# TIDA-01576_ADS8686S_AFE_Pg6-Current_Meas.net
KiCad netlist of a schematic drawn in Altium Designer
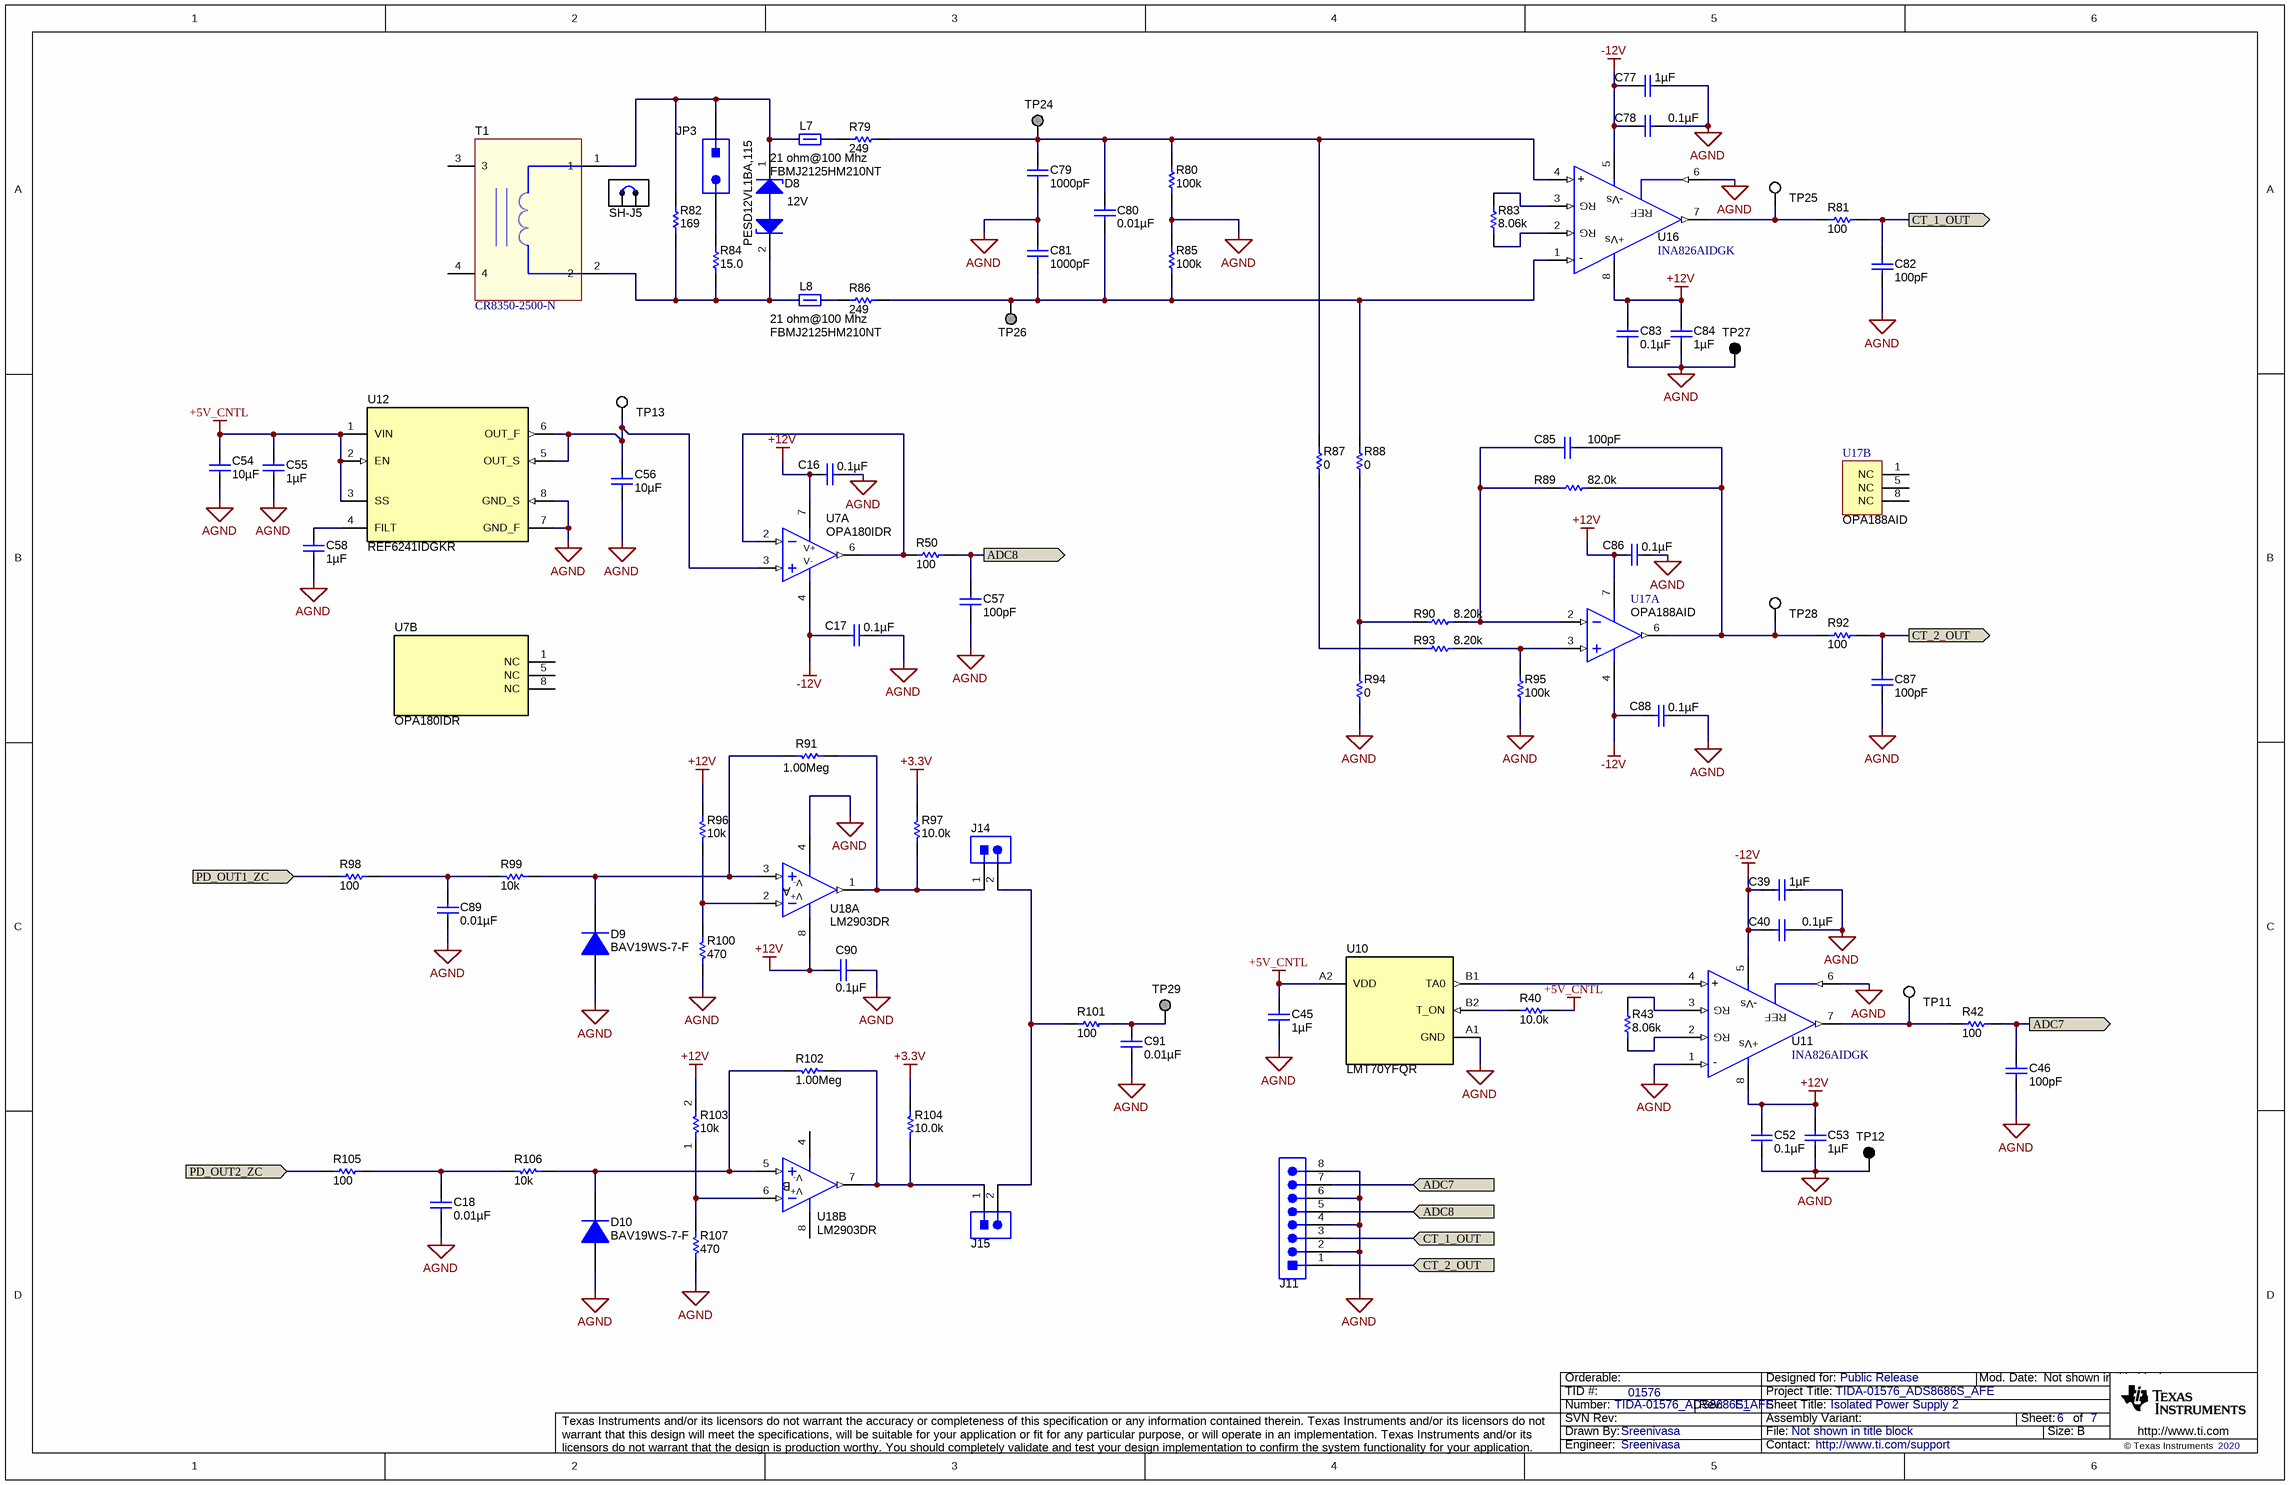
[diagram p0: TIDA-01576_ADS8686S_AFE_Pg6-Current Measurement and ZCD for Coherent Sampling.SchDoc]

(export (version "E")
  (design (tool "Eeschema 10.0.6"))
  (components
    (comp (ref "C16")
      (value "06033C104JAT2A")
      (footprint "0603")
      (description "CAP, CERM, 0.1uF, 25V, +/-5%, X7R, 0603")
      (fields
        (field (name "VALUEDISPLAYED") "0.1µF")
        (field (name "MANUFACTURER") "AVX")
        (field (name "PUBLISHER") "Texas Instruments")
      )
      (libsource (lib "Capacitor_Ceramic") (part "06033C104JAT2A"))
    )
    (comp (ref "C17")
      (value "06033C104JAT2A")
      (footprint "0603")
      (description "CAP, CERM, 0.1uF, 25V, +/-5%, X7R, 0603")
      (fields
        (field (name "VALUEDISPLAYED") "0.1µF")
        (field (name "MANUFACTURER") "AVX")
        (field (name "PUBLISHER") "Texas Instruments")
      )
      (libsource (lib "Capacitor_Ceramic") (part "06033C104JAT2A"))
    )
    (comp (ref "C18")
      (value "C1608C0G1E103J080AA")
      (footprint "0603")
      (description "CAP, CERM, 0.01uF, 25V, +/-5%, C0G/NP0, 0603")
      (fields
        (field (name "VALUEDISPLAYED") "0.01µF")
        (field (name "MANUFACTURER") "TDK")
        (field (name "PUBLISHER") "Texas Instruments")
      )
      (libsource (lib "Capacitor_Ceramic") (part "C1608C0G1E103J"))
    )
    (comp (ref "C39")
      (value "GRM188R61C105KA93D")
      (footprint "0603")
      (description "CAP, CERM, 1 µF, 16 V, +/- 10%, X5R, 0603")
      (fields
        (field (name "VALUEDISPLAYED") "1µF")
        (field (name "MANUFACTURER") "Murata")
        (field (name "PUBLISHER") "Texas Instruments")
      )
      (libsource (lib "Capacitor_Ceramic") (part "C1608X5R1C105K"))
    )
    (comp (ref "C40")
      (value "CGA3E2X8R1E104K080AA")
      (footprint "0603")
      (description "CAP, CERM, 0.1 µF, 25 V, +/- 10%, X8R, AEC-Q200 Grade 0, 0603")
      (fields
        (field (name "VALUEDISPLAYED") "0.1µF")
        (field (name "MANUFACTURER") "TDK")
        (field (name "PUBLISHER") "Texas Instruments")
      )
      (libsource (lib "Capacitor_Ceramic") (part "CGA3E2X8R1E104K080AA"))
    )
    (comp (ref "C45")
      (value "GRM188R61E105KA12D")
      (footprint "0603")
      (description "CAP, CERM, 1 µF, 25 V, +/- 10%, X5R, 0603")
      (fields
        (field (name "VALUEDISPLAYED") "1µF")
        (field (name "MANUFACTURER") "MuRata")
        (field (name "PUBLISHER") "Texas Instruments")
      )
      (libsource (lib "Capacitor_Ceramic") (part "GRM188R61E105KA12D"))
    )
    (comp (ref "C46")
      (value "06033C101KAT2A")
      (footprint "0603")
      (description "CAP, CERM, 100pF, 25V, +/-10%, X7R, 0603")
      (fields
        (field (name "VALUEDISPLAYED") "100pF")
        (field (name "MANUFACTURER") "AVX")
        (field (name "PUBLISHER") "Texas Instruments")
      )
      (libsource (lib "Capacitor_Ceramic") (part "06033C101KAT2A"))
    )
    (comp (ref "C52")
      (value "CGA3E2X8R1E104K080AA")
      (footprint "0603")
      (description "CAP, CERM, 0.1 µF, 25 V, +/- 10%, X8R, AEC-Q200 Grade 0, 0603")
      (fields
        (field (name "VALUEDISPLAYED") "0.1µF")
        (field (name "MANUFACTURER") "TDK")
        (field (name "PUBLISHER") "Texas Instruments")
      )
      (libsource (lib "Capacitor_Ceramic") (part "CGA3E2X8R1E104K080AA"))
    )
    (comp (ref "C53")
      (value "GRM188R61C105KA93D")
      (footprint "0603")
      (description "CAP, CERM, 1 µF, 16 V, +/- 10%, X5R, 0603")
      (fields
        (field (name "VALUEDISPLAYED") "1µF")
        (field (name "MANUFACTURER") "Murata")
        (field (name "PUBLISHER") "Texas Instruments")
      )
      (libsource (lib "Capacitor_Ceramic") (part "C1608X5R1C105K"))
    )
    (comp (ref "C54")
      (value "~")
      (footprint "1210")
      (description "CAP, CERM, 10uF, 35V, +/-20%, X7R, 1210")
      (fields
        (field (name "PARTNUMBER") "GMK325AB7106MM-T")
        (field (name "VALUEDISPLAYED") "10µF")
        (field (name "MANUFACTURER") "Taiyo Yuden")
        (field (name "PUBLISHER") "Texas Instruments")
      )
      (libsource (lib "Capacitor_Ceramic") (part "GMK325AB7106MM-T"))
    )
    (comp (ref "C55")
      (value "GRM188R61E105KA12D")
      (footprint "0603")
      (description "CAP, CERM, 1 µF, 25 V, +/- 10%, X5R, 0603")
      (fields
        (field (name "VALUEDISPLAYED") "1µF")
        (field (name "MANUFACTURER") "MuRata")
        (field (name "PUBLISHER") "Texas Instruments")
      )
      (libsource (lib "Capacitor_Ceramic") (part "GRM188R61E105KA12D"))
    )
    (comp (ref "C56")
      (value "~")
      (footprint "1210")
      (description "CAP, CERM, 10uF, 35V, +/-20%, X7R, 1210")
      (fields
        (field (name "PARTNUMBER") "GMK325AB7106MM-T")
        (field (name "VALUEDISPLAYED") "10µF")
        (field (name "MANUFACTURER") "Taiyo Yuden")
        (field (name "PUBLISHER") "Texas Instruments")
      )
      (libsource (lib "Capacitor_Ceramic") (part "GMK325AB7106MM-T"))
    )
    (comp (ref "C57")
      (value "06033C101KAT2A")
      (footprint "0603")
      (description "CAP, CERM, 100pF, 25V, +/-10%, X7R, 0603")
      (fields
        (field (name "VALUEDISPLAYED") "100pF")
        (field (name "MANUFACTURER") "AVX")
        (field (name "PUBLISHER") "Texas Instruments")
      )
      (libsource (lib "Capacitor_Ceramic") (part "06033C101KAT2A"))
    )
    (comp (ref "C58")
      (value "GRM188R61E105KA12D")
      (footprint "0603")
      (description "CAP, CERM, 1 µF, 25 V, +/- 10%, X5R, 0603")
      (fields
        (field (name "VALUEDISPLAYED") "1µF")
        (field (name "MANUFACTURER") "MuRata")
        (field (name "PUBLISHER") "Texas Instruments")
      )
      (libsource (lib "Capacitor_Ceramic") (part "GRM188R61E105KA12D"))
    )
    (comp (ref "C77")
      (value "GRM188R61C105KA93D")
      (footprint "0603")
      (description "CAP, CERM, 1 µF, 16 V, +/- 10%, X5R, 0603")
      (fields
        (field (name "VALUEDISPLAYED") "1µF")
        (field (name "MANUFACTURER") "Murata")
        (field (name "PUBLISHER") "Texas Instruments")
      )
      (libsource (lib "Capacitor_Ceramic") (part "C1608X5R1C105K"))
    )
    (comp (ref "C78")
      (value "CGA3E2X8R1E104K080AA")
      (footprint "0603")
      (description "CAP, CERM, 0.1 µF, 25 V, +/- 10%, X8R, AEC-Q200 Grade 0, 0603")
      (fields
        (field (name "VALUEDISPLAYED") "0.1µF")
        (field (name "MANUFACTURER") "TDK")
        (field (name "PUBLISHER") "Texas Instruments")
      )
      (libsource (lib "Capacitor_Ceramic") (part "CGA3E2X8R1E104K080AA"))
    )
    (comp (ref "C79")
      (value "C0603X102K5RACTU")
      (footprint "0603")
      (description "CAP, CERM, 1000 pF, 50 V, +/- 10%, X7R, 0603")
      (fields
        (field (name "VALUEDISPLAYED") "1000pF")
        (field (name "MANUFACTURER") "Kemet")
        (field (name "PUBLISHER") "Texas Instruments")
      )
      (libsource (lib "Capacitor_Ceramic") (part "C0603X102K5RACTU"))
    )
    (comp (ref "C80")
      (value "06031C103KAT2A")
      (footprint "0603")
      (description "10000pF 100V Ceramic Capacitor X7R 0603")
      (fields
        (field (name "VALUEDISPLAYED") "0.01µF")
        (field (name "MANUFACTURER") "AVX")
        (field (name "PUBLISHER") "Texas Instruments")
      )
      (libsource (lib "Capacitor_Ceramic") (part "06031C103JAT2A"))
    )
    (comp (ref "C81")
      (value "C0603X102K5RACTU")
      (footprint "0603")
      (description "CAP, CERM, 1000 pF, 50 V, +/- 10%, X7R, 0603")
      (fields
        (field (name "VALUEDISPLAYED") "1000pF")
        (field (name "MANUFACTURER") "Kemet")
        (field (name "PUBLISHER") "Texas Instruments")
      )
      (libsource (lib "Capacitor_Ceramic") (part "C0603X102K5RACTU"))
    )
    (comp (ref "C82")
      (value "06033C101KAT2A")
      (footprint "0603")
      (description "CAP, CERM, 100pF, 25V, +/-10%, X7R, 0603")
      (fields
        (field (name "VALUEDISPLAYED") "100pF")
        (field (name "MANUFACTURER") "AVX")
        (field (name "PUBLISHER") "Texas Instruments")
      )
      (libsource (lib "Capacitor_Ceramic") (part "06033C101KAT2A"))
    )
    (comp (ref "C83")
      (value "CGA3E2X8R1E104K080AA")
      (footprint "0603")
      (description "CAP, CERM, 0.1 µF, 25 V, +/- 10%, X8R, AEC-Q200 Grade 0, 0603")
      (fields
        (field (name "VALUEDISPLAYED") "0.1µF")
        (field (name "MANUFACTURER") "TDK")
        (field (name "PUBLISHER") "Texas Instruments")
      )
      (libsource (lib "Capacitor_Ceramic") (part "CGA3E2X8R1E104K080AA"))
    )
    (comp (ref "C84")
      (value "GRM188R61C105KA93D")
      (footprint "0603")
      (description "CAP, CERM, 1 µF, 16 V, +/- 10%, X5R, 0603")
      (fields
        (field (name "VALUEDISPLAYED") "1µF")
        (field (name "MANUFACTURER") "Murata")
        (field (name "PUBLISHER") "Texas Instruments")
      )
      (libsource (lib "Capacitor_Ceramic") (part "C1608X5R1C105K"))
    )
    (comp (ref "C85")
      (value "06033C101KAT2A")
      (footprint "0603")
      (description "CAP, CERM, 100pF, 25V, +/-10%, X7R, 0603")
      (fields
        (field (name "VALUEDISPLAYED") "100pF")
        (field (name "MANUFACTURER") "AVX")
        (field (name "PUBLISHER") "Texas Instruments")
      )
      (libsource (lib "Capacitor_Ceramic") (part "06033C101KAT2A"))
    )
    (comp (ref "C86")
      (value "06033C104JAT2A")
      (footprint "0603")
      (description "CAP, CERM, 0.1uF, 25V, +/-5%, X7R, 0603")
      (fields
        (field (name "VALUEDISPLAYED") "0.1µF")
        (field (name "MANUFACTURER") "AVX")
        (field (name "PUBLISHER") "Texas Instruments")
      )
      (libsource (lib "Capacitor_Ceramic") (part "06033C104JAT2A"))
    )
    (comp (ref "C87")
      (value "06033C101KAT2A")
      (footprint "0603")
      (description "CAP, CERM, 100pF, 25V, +/-10%, X7R, 0603")
      (fields
        (field (name "VALUEDISPLAYED") "100pF")
        (field (name "MANUFACTURER") "AVX")
        (field (name "PUBLISHER") "Texas Instruments")
      )
      (libsource (lib "Capacitor_Ceramic") (part "06033C101KAT2A"))
    )
    (comp (ref "C88")
      (value "06033C104JAT2A")
      (footprint "0603")
      (description "CAP, CERM, 0.1uF, 25V, +/-5%, X7R, 0603")
      (fields
        (field (name "VALUEDISPLAYED") "0.1µF")
        (field (name "MANUFACTURER") "AVX")
        (field (name "PUBLISHER") "Texas Instruments")
      )
      (libsource (lib "Capacitor_Ceramic") (part "06033C104JAT2A"))
    )
    (comp (ref "C89")
      (value "C1608C0G1E103J080AA")
      (footprint "0603")
      (description "CAP, CERM, 0.01uF, 25V, +/-5%, C0G/NP0, 0603")
      (fields
        (field (name "VALUEDISPLAYED") "0.01µF")
        (field (name "MANUFACTURER") "TDK")
        (field (name "PUBLISHER") "Texas Instruments")
      )
      (libsource (lib "Capacitor_Ceramic") (part "C1608C0G1E103J"))
    )
    (comp (ref "C90")
      (value "06033C104JAT2A")
      (footprint "0603")
      (description "CAP, CERM, 0.1uF, 25V, +/-5%, X7R, 0603")
      (fields
        (field (name "VALUEDISPLAYED") "0.1µF")
        (field (name "MANUFACTURER") "AVX")
        (field (name "PUBLISHER") "Texas Instruments")
      )
      (libsource (lib "Capacitor_Ceramic") (part "06033C104JAT2A"))
    )
    (comp (ref "C91")
      (value "C1608C0G1E103J080AA")
      (footprint "0603")
      (description "CAP, CERM, 0.01uF, 25V, +/-5%, C0G/NP0, 0603")
      (fields
        (field (name "VALUEDISPLAYED") "0.01µF")
        (field (name "MANUFACTURER") "TDK")
        (field (name "PUBLISHER") "Texas Instruments")
      )
      (libsource (lib "Capacitor_Ceramic") (part "C1608C0G1E103J"))
    )
    (comp (ref "D8")
      (value "12V")
      (footprint "SOD-323")
      (description "TVS DIODE 12VWM 37VC SOD323")
      (fields
        (field (name "PARTNUMBER") "PESD12VL1BA,115")
        (field (name "MANUFACTURER") "NXP Semiconductor")
        (field (name "Comment") "PESD12VL1BA,115")
        (field (name "SYMBOLCREATOR") "x0199378")
      )
      (libsource (lib "PESD3V3L1BA") (part "PESD3V3L1BA"))
    )
    (comp (ref "D9")
      (value "BAV19WS-7-F")
      (footprint "SOD-323")
      (description "Diode, Switching, 100 V, 0.2 A, SOD-323")
      (fields (field (name "MANUFACTURER") "Diodes Inc.") (field (name "PUBLISHER") "Texas Instruments"))
      (libsource (lib "Diode") (part "BAV19WS-7-F"))
    )
    (comp (ref "D10")
      (value "BAV19WS-7-F")
      (footprint "SOD-323")
      (description "Diode, Switching, 100 V, 0.2 A, SOD-323")
      (fields (field (name "MANUFACTURER") "Diodes Inc.") (field (name "PUBLISHER") "Texas Instruments"))
      (libsource (lib "Diode") (part "BAV19WS-7-F"))
    )
    (comp (ref "J11")
      (value "1803332")
      (footprint "Phoenix_1803332")
      (description "Header(shrouded), 3.81mm, 8x1, Tin, R/A, TH")
      (fields (field (name "MANUFACTURER") "Phoenix Contact"))
      (libsource (lib "Altium Vault - TI") (part "CMP-0078749-1"))
    )
    (comp (ref "J14")
      (value "PEC02SAAN")
      (footprint "CONN_PEC02SAAN")
      (description "Header, 100mil, 2x1, Tin, TH")
      (fields
        (field (name "MANUFACTURER") "Sullins Connector Solutions")
        (field (name "SYMBOLCREATOR") "a0412235")
        (field (name "PUBLISHER") "Texas Instruments")
      )
      (libsource (lib "Connectors_Sullins") (part "PEC02SAAN"))
    )
    (comp (ref "J15")
      (value "PEC02SAAN")
      (footprint "CONN_PEC02SAAN")
      (description "Header, 100mil, 2x1, Tin, TH")
      (fields
        (field (name "MANUFACTURER") "Sullins Connector Solutions")
        (field (name "SYMBOLCREATOR") "a0412235")
        (field (name "PUBLISHER") "Texas Instruments")
      )
      (libsource (lib "") (part "PEC02SAAN_1"))
    )
    (comp (ref "JP3")
      (value "5-146280-2")
      (footprint "TSW-102-07-G-S")
      (description "Header, 100mil, 2x1, Gold, TH")
      (fields
        (field (name "MANUFACTURER") "TE Connectivity")
        (field (name "SYMBOLCREATOR") "a0412235")
        (field (name "PUBLISHER") "Texas Instruments")
      )
      (libsource (lib "Connectors_Samtec") (part "TSW-102-07-G-S"))
    )
    (comp (ref "L7")
      (value "21 ohm@100 Mhz")
      (footprint "0805_HV")
      (description "Ferrite Bead, 21 ohm @ 100 MHz, 6 A, 0805")
      (fields
        (field (name "PARTNUMBER") "FBMJ2125HM210NT")
        (field (name "MANUFACTURER") "Taiyo Yuden")
        (field (name "Comment") "FBMJ2125HM210NT")
        (field (name "PUBLISHER") "Texas Instruments")
      )
      (libsource (lib "FerriteBead") (part "FBMJ2125HM210NT"))
    )
    (comp (ref "L8")
      (value "21 ohm@100 Mhz")
      (footprint "0805_HV")
      (description "Ferrite Bead, 21 ohm @ 100 MHz, 6 A, 0805")
      (fields
        (field (name "PARTNUMBER") "FBMJ2125HM210NT")
        (field (name "MANUFACTURER") "Taiyo Yuden")
        (field (name "Comment") "FBMJ2125HM210NT")
        (field (name "PUBLISHER") "Texas Instruments")
      )
      (libsource (lib "FerriteBead") (part "FBMJ2125HM210NT"))
    )
    (comp (ref "R40")
      (value "RG1608P-103-B-T5")
      (footprint "0603")
      (description "RES, 10.0 k, 0.1%, 0.1 W, 0603")
      (fields
        (field (name "VALUEDISPLAYED") "10.0k")
        (field (name "MANUFACTURER") "Susumu Co Ltd")
        (field (name "PUBLISHER") "Texas Instruments")
      )
      (libsource (lib "Resistor_0603") (part "RG1608P-103-B-T5"))
    )
    (comp (ref "R42")
      (value "RG1608P-101-B-T5")
      (footprint "0603")
      (description "RES, 100, 0.1%, 0.1 W, 0603")
      (fields
        (field (name "VALUEDISPLAYED") "100")
        (field (name "MANUFACTURER") "Susumu Co Ltd")
        (field (name "PUBLISHER") "Texas Instruments")
      )
      (libsource (lib "Resistor_0603") (part "RG1608P-101-B-T5"))
    )
    (comp (ref "R43")
      (value "RG1608P-8061-B-T5")
      (footprint "0603")
      (description "RES, 8.06 k, 0.1%, 0.1 W, 0603")
      (fields
        (field (name "VALUEDISPLAYED") "8.06k")
        (field (name "MANUFACTURER") "Susumu Co Ltd")
        (field (name "PUBLISHER") "Texas Instruments")
      )
      (libsource (lib "Resistor_0603") (part "RG1608P-8061-B-T5"))
    )
    (comp (ref "R50")
      (value "RG1608P-101-B-T5")
      (footprint "0603")
      (description "RES, 100, 0.1%, 0.1 W, 0603")
      (fields
        (field (name "VALUEDISPLAYED") "100")
        (field (name "MANUFACTURER") "Susumu Co Ltd")
        (field (name "PUBLISHER") "Texas Instruments")
      )
      (libsource (lib "Resistor_0603") (part "RG1608P-101-B-T5"))
    )
    (comp (ref "R79")
      (value "RT0603BRD07249RL")
      (footprint "0603")
      (description "RES, 249, 0.1%, 0.1 W, 0603")
      (fields
        (field (name "VALUEDISPLAYED") "249")
        (field (name "MANUFACTURER") "Yageo America")
        (field (name "PUBLISHER") "Texas Instruments")
      )
      (libsource (lib "Resistor_0603") (part "RT0603BRD07249RL"))
    )
    (comp (ref "R80")
      (value "RG1608P-104-B-T5")
      (footprint "0603")
      (description "RES, 100 k, 0.1%, 0.1 W, 0603")
      (fields
        (field (name "VALUEDISPLAYED") "100k")
        (field (name "MANUFACTURER") "Susumu Co Ltd")
        (field (name "PUBLISHER") "Texas Instruments")
      )
      (libsource (lib "Resistor_0603") (part "RG1608P-104-B-T5"))
    )
    (comp (ref "R81")
      (value "RG1608P-101-B-T5")
      (footprint "0603")
      (description "RES, 100, 0.1%, 0.1 W, 0603")
      (fields
        (field (name "VALUEDISPLAYED") "100")
        (field (name "MANUFACTURER") "Susumu Co Ltd")
        (field (name "PUBLISHER") "Texas Instruments")
      )
      (libsource (lib "Resistor_0603") (part "RG1608P-101-B-T5"))
    )
    (comp (ref "R82")
      (value "RC0603FR-07169RL")
      (footprint "0603")
      (description "RES, 169, 1%, 0.1 W, 0603")
      (fields
        (field (name "VALUEDISPLAYED") "169")
        (field (name "MANUFACTURER") "Yageo America")
        (field (name "PUBLISHER") "Texas Instruments")
      )
      (libsource (lib "Resistor_0603") (part "RC0603FR-07169RL"))
    )
    (comp (ref "R83")
      (value "RG1608P-8061-B-T5")
      (footprint "0603")
      (description "RES, 8.06 k, 0.1%, 0.1 W, 0603")
      (fields
        (field (name "VALUEDISPLAYED") "8.06k")
        (field (name "MANUFACTURER") "Susumu Co Ltd")
        (field (name "PUBLISHER") "Texas Instruments")
      )
      (libsource (lib "Resistor_0603") (part "RG1608P-8061-B-T5"))
    )
    (comp (ref "R84")
      (value "CPF-A-0603B15RE")
      (footprint "CPF0603")
      (description "RES, 15.0, 0.1%, 0.063 W, AEC-Q200 Grade 0, 0603")
      (fields
        (field (name "VALUEDISPLAYED") "15.0")
        (field (name "MANUFACTURER") "TE Connectivity")
        (field (name "PUBLISHER") "Texas Instruments")
      )
      (libsource (lib "Resistor_0603") (part "CPF-A-0603B15RE"))
    )
    (comp (ref "R85")
      (value "RG1608P-104-B-T5")
      (footprint "0603")
      (description "RES, 100 k, 0.1%, 0.1 W, 0603")
      (fields
        (field (name "VALUEDISPLAYED") "100k")
        (field (name "MANUFACTURER") "Susumu Co Ltd")
        (field (name "PUBLISHER") "Texas Instruments")
      )
      (libsource (lib "Resistor_0603") (part "RG1608P-104-B-T5"))
    )
    (comp (ref "R86")
      (value "RT0603BRD07249RL")
      (footprint "0603")
      (description "RES, 249, 0.1%, 0.1 W, 0603")
      (fields
        (field (name "VALUEDISPLAYED") "249")
        (field (name "MANUFACTURER") "Yageo America")
        (field (name "PUBLISHER") "Texas Instruments")
      )
      (libsource (lib "Resistor_0603") (part "RT0603BRD07249RL"))
    )
    (comp (ref "R87")
      (value "RC0603JR-070RL")
      (footprint "0603")
      (description "RES, 0, 5%, 0.1 W, 0603")
      (fields
        (field (name "VALUEDISPLAYED") "0")
        (field (name "MANUFACTURER") "Yageo America")
        (field (name "PUBLISHER") "Texas Instruments")
      )
      (libsource (lib "Resistor_0603") (part "RC0603JR-070RL"))
    )
    (comp (ref "R88")
      (value "RC0603JR-070RL")
      (footprint "0603")
      (description "RES, 0, 5%, 0.1 W, 0603")
      (fields
        (field (name "VALUEDISPLAYED") "0")
        (field (name "MANUFACTURER") "Yageo America")
        (field (name "PUBLISHER") "Texas Instruments")
      )
      (libsource (lib "Resistor_0603") (part "RC0603JR-070RL"))
    )
    (comp (ref "R89")
      (value "RG1608P-823-B-T5")
      (footprint "0603")
      (description "RES, 82.0 k, 0.1%, 0.1 W, 0603")
      (fields
        (field (name "VALUEDISPLAYED") "82.0k")
        (field (name "MANUFACTURER") "Susumu Co Ltd")
        (field (name "PUBLISHER") "Texas Instruments")
      )
      (libsource (lib "Resistor_0603") (part "RG1608P-823-B-T5"))
    )
    (comp (ref "R90")
      (value "RG1608P-822-B-T5")
      (footprint "0603")
      (description "RES, 8.20 k, 0.1%, 0.1 W, 0603")
      (fields
        (field (name "VALUEDISPLAYED") "8.20k")
        (field (name "MANUFACTURER") "Susumu Co Ltd")
        (field (name "PUBLISHER") "Texas Instruments")
      )
      (libsource (lib "Resistor_0603") (part "RG1608P-822-B-T5"))
    )
    (comp (ref "R91")
      (value "1.00Meg")
      (footprint "0603")
      (description "RES, 1.00Meg ohm, 1%, 0.1W, 0603")
      (fields
        (field (name "PARTNUMBER") "CRCW06031M00FKEA")
        (field (name "MANUFACTURER") "Vishay-Dale")
        (field (name "PUBLISHER") "Texas Instruments")
      )
      (libsource (lib "Resistor_0603") (part "CRCW06031M00FKEA"))
    )
    (comp (ref "R92")
      (value "RG1608P-101-B-T5")
      (footprint "0603")
      (description "RES, 100, 0.1%, 0.1 W, 0603")
      (fields
        (field (name "VALUEDISPLAYED") "100")
        (field (name "MANUFACTURER") "Susumu Co Ltd")
        (field (name "PUBLISHER") "Texas Instruments")
      )
      (libsource (lib "Resistor_0603") (part "RG1608P-101-B-T5"))
    )
    (comp (ref "R93")
      (value "RG1608P-822-B-T5")
      (footprint "0603")
      (description "RES, 8.20 k, 0.1%, 0.1 W, 0603")
      (fields
        (field (name "VALUEDISPLAYED") "8.20k")
        (field (name "MANUFACTURER") "Susumu Co Ltd")
        (field (name "PUBLISHER") "Texas Instruments")
      )
      (libsource (lib "Resistor_0603") (part "RG1608P-822-B-T5"))
    )
    (comp (ref "R94")
      (value "RC0603JR-070RL")
      (footprint "0603")
      (description "RES, 0, 5%, 0.1 W, 0603")
      (fields
        (field (name "VALUEDISPLAYED") "0")
        (field (name "MANUFACTURER") "Yageo America")
        (field (name "PUBLISHER") "Texas Instruments")
      )
      (libsource (lib "Resistor_0603") (part "RC0603JR-070RL"))
    )
    (comp (ref "R95")
      (value "RG1608P-104-B-T5")
      (footprint "0603")
      (description "RES, 100 k, 0.1%, 0.1 W, 0603")
      (fields
        (field (name "VALUEDISPLAYED") "100k")
        (field (name "MANUFACTURER") "Susumu Co Ltd")
        (field (name "PUBLISHER") "Texas Instruments")
      )
      (libsource (lib "Resistor_0603") (part "RG1608P-104-B-T5"))
    )
    (comp (ref "R96")
      (value "10k")
      (footprint "0603")
      (description "RES, 10.0k ohm, 1%, 0.1W, 0603")
      (fields
        (field (name "PARTNUMBER") "CRCW060310K0FKEA")
        (field (name "MANUFACTURER") "Stackpole Electronics Inc")
        (field (name "PUBLISHER") "Texas Instruments")
      )
      (libsource (lib "Resistor_0603") (part "RNCF0603TKY10K0"))
    )
    (comp (ref "R97")
      (value "10.0k")
      (footprint "0603")
      (description "RES, 10.0k ohm, 1%, 0.1W, 0603")
      (fields
        (field (name "PARTNUMBER") "CRCW060310K0FKEA")
        (field (name "MANUFACTURER") "Vishay-Dale")
        (field (name "PUBLISHER") "Texas Instruments")
      )
      (libsource (lib "Resistor_0603") (part "CRCW060310K0FKEA"))
    )
    (comp (ref "R98")
      (value "100")
      (footprint "0603")
      (description "RES, 100 ohm, 1%, 0.1W, 0603")
      (fields
        (field (name "PARTNUMBER") "CRCW0603100RFKEA")
        (field (name "MANUFACTURER") "Vishay-Dale")
        (field (name "PUBLISHER") "Texas Instruments")
      )
      (libsource (lib "Resistor_0603") (part "CRCW0603100RFKEA"))
    )
    (comp (ref "R99")
      (value "10k")
      (footprint "0603")
      (description "RES, 10.0k ohm, 1%, 0.1W, 0603")
      (fields
        (field (name "PARTNUMBER") "CRCW060310K0FKEA")
        (field (name "MANUFACTURER") "Stackpole Electronics Inc")
        (field (name "PUBLISHER") "Texas Instruments")
      )
      (libsource (lib "Resistor_0603") (part "RNCF0603TKY10K0"))
    )
    (comp (ref "R100")
      (value "RC1206FR-07470RL")
      (footprint "1206")
      (description "RES, 470, 1%, 0.25 W, 1206")
      (fields
        (field (name "MANUFACTURER") "Yageo America")
        (field (name "VALUEDISPLAYED") "470")
        (field (name "PUBLISHER") "Texas Instruments")
      )
      (libsource (lib "Resistor_1206") (part "RC1206FR-07470RL"))
    )
    (comp (ref "R101")
      (value "100")
      (footprint "0603")
      (description "RES, 100 ohm, 1%, 0.1W, 0603")
      (fields
        (field (name "PARTNUMBER") "CRCW0603100RFKEA")
        (field (name "MANUFACTURER") "Vishay-Dale")
        (field (name "PUBLISHER") "Texas Instruments")
      )
      (libsource (lib "Resistor_0603") (part "CRCW0603100RFKEA"))
    )
    (comp (ref "R102")
      (value "1.00Meg")
      (footprint "0603")
      (description "RES, 1.00Meg ohm, 1%, 0.1W, 0603")
      (fields
        (field (name "PARTNUMBER") "CRCW06031M00FKEA")
        (field (name "MANUFACTURER") "Vishay-Dale")
        (field (name "PUBLISHER") "Texas Instruments")
      )
      (libsource (lib "Resistor_0603") (part "CRCW06031M00FKEA"))
    )
    (comp (ref "R103")
      (value "10k")
      (footprint "0603")
      (description "RES, 10.0k ohm, 1%, 0.1W, 0603")
      (fields
        (field (name "PARTNUMBER") "CRCW060310K0FKEA")
        (field (name "MANUFACTURER") "Stackpole Electronics Inc")
        (field (name "PUBLISHER") "Texas Instruments")
      )
      (libsource (lib "") (part "RNCF0603TKY10K0_1"))
    )
    (comp (ref "R104")
      (value "10.0k")
      (footprint "0603")
      (description "RES, 10.0k ohm, 1%, 0.1W, 0603")
      (fields
        (field (name "PARTNUMBER") "CRCW060310K0FKEA")
        (field (name "MANUFACTURER") "Vishay-Dale")
        (field (name "PUBLISHER") "Texas Instruments")
      )
      (libsource (lib "Resistor_0603") (part "CRCW060310K0FKEA"))
    )
    (comp (ref "R105")
      (value "100")
      (footprint "0603")
      (description "RES, 100 ohm, 1%, 0.1W, 0603")
      (fields
        (field (name "PARTNUMBER") "CRCW0603100RFKEA")
        (field (name "MANUFACTURER") "Vishay-Dale")
        (field (name "PUBLISHER") "Texas Instruments")
      )
      (libsource (lib "Resistor_0603") (part "CRCW0603100RFKEA"))
    )
    (comp (ref "R106")
      (value "10k")
      (footprint "0603")
      (description "RES, 10.0k ohm, 1%, 0.1W, 0603")
      (fields
        (field (name "PARTNUMBER") "CRCW060310K0FKEA")
        (field (name "MANUFACTURER") "Stackpole Electronics Inc")
        (field (name "PUBLISHER") "Texas Instruments")
      )
      (libsource (lib "Resistor_0603") (part "RNCF0603TKY10K0"))
    )
    (comp (ref "R107")
      (value "RC1206FR-07470RL")
      (footprint "1206")
      (description "RES, 470, 1%, 0.25 W, 1206")
      (fields
        (field (name "MANUFACTURER") "Yageo America")
        (field (name "VALUEDISPLAYED") "470")
        (field (name "PUBLISHER") "Texas Instruments")
      )
      (libsource (lib "Resistor_1206") (part "RC1206FR-07470RL"))
    )
    (comp (ref "SH-J5")
      (value "881545-2")
      (footprint "TE_881545-2")
      (description "Shunt, 100mil, Gold plated, Black")
      (fields (field (name "MANUFACTURER") "TE Connectivity") (field (name "PUBLISHER") "Texas Instruments"))
      (libsource (lib "Hardware") (part "881545-2"))
    )
    (comp (ref "T1")
      (value "CR8350-2500-N")
      (footprint "XFMR_CR8350-2500-N")
      (description "CURRENT TRANSFORMER, 20-1 KHz, 57 OHM, VERTICAL, THRU-4P")
      (fields (field (name "MANUFACTURER") "CR MAGNETICS") (field (name "SYMBOLCREATOR") "x0199378"))
      (libsource (lib "CR8350-2500-N") (part "CR8350-2500-N"))
    )
    (comp (ref "TP11")
      (value "5002")
      (footprint "Keystone5002")
      (description "Test Point, Miniature, White, TH")
      (fields (field (name "MANUFACTURER") "Keystone") (field (name "PUBLISHER") "Texas Instruments"))
      (libsource (lib "Connectors_Keystone") (part "5002"))
    )
    (comp (ref "TP12")
      (value "5001")
      (footprint "Keystone5001")
      (description "Test Point, Miniature, Black, TH")
      (fields (field (name "MANUFACTURER") "Keystone") (field (name "PUBLISHER") "Texas Instruments"))
      (libsource (lib "Connectors_Keystone") (part "5001"))
    )
    (comp (ref "TP13")
      (value "5002")
      (footprint "Keystone5002")
      (description "Test Point, Miniature, White, TH")
      (fields (field (name "MANUFACTURER") "Keystone") (field (name "PUBLISHER") "Texas Instruments"))
      (libsource (lib "Connectors_Keystone") (part "5002"))
    )
    (comp (ref "TP24")
      (value "Suggest using a net name here")
      (footprint "Keystone1573-2")
      (description "Terminal, Turret, TH, Double")
      (fields
        (field (name "PARTNUMBER") "1573-2")
        (field (name "MANUFACTURER") "Keystone")
        (field (name "PUBLISHER") "Texas Instruments")
      )
      (libsource (lib "Connectors_Keystone") (part "1573-2"))
    )
    (comp (ref "TP25")
      (value "5002")
      (footprint "Keystone5002")
      (description "Test Point, Miniature, White, TH")
      (fields (field (name "MANUFACTURER") "Keystone") (field (name "PUBLISHER") "Texas Instruments"))
      (libsource (lib "Connectors_Keystone") (part "5002"))
    )
    (comp (ref "TP26")
      (value "Suggest using a net name here")
      (footprint "Keystone1573-2")
      (description "Terminal, Turret, TH, Double")
      (fields
        (field (name "PARTNUMBER") "1573-2")
        (field (name "MANUFACTURER") "Keystone")
        (field (name "PUBLISHER") "Texas Instruments")
      )
      (libsource (lib "Connectors_Keystone") (part "1573-2"))
    )
    (comp (ref "TP27")
      (value "5001")
      (footprint "Keystone5001")
      (description "Test Point, Miniature, Black, TH")
      (fields (field (name "MANUFACTURER") "Keystone") (field (name "PUBLISHER") "Texas Instruments"))
      (libsource (lib "Connectors_Keystone") (part "5001"))
    )
    (comp (ref "TP28")
      (value "5002")
      (footprint "Keystone5002")
      (description "Test Point, Miniature, White, TH")
      (fields (field (name "MANUFACTURER") "Keystone") (field (name "PUBLISHER") "Texas Instruments"))
      (libsource (lib "Connectors_Keystone") (part "5002"))
    )
    (comp (ref "TP29")
      (value "Suggest using a net name here")
      (footprint "Keystone1573-2")
      (description "Terminal, Turret, TH, Double")
      (fields
        (field (name "PARTNUMBER") "1573-2")
        (field (name "MANUFACTURER") "Keystone")
        (field (name "PUBLISHER") "Texas Instruments")
      )
      (libsource (lib "Connectors_Keystone") (part "1573-2"))
    )
    (comp (ref "U7")
      (value "OPA180IDR")
      (footprint "D0008A_N")
      (fields
        (field (name "ALTERNATE PARTNUMBER") "OPA180ID")
        (field (name "MANUFACTURER") "Texas Instruments")
        (field (name "PARTNUMBER") "OPA180IDR")
        (field (name "PUBLISHER") "Texas Instruments")
      )
      (libsource (lib "Altium Vault - TI") (part "OpAmp_Single"))
    )
    (comp (ref "U10")
      (value "LMT70YFQR")
      (footprint "YFQ0004ACAC")
      (description "+/-0.1degC Precision Analog Temperature Sensor, YFQ0004ACAC (DSBGA-4)")
      (fields
        (field (name "ALTERNATE PARTNUMBER") "LMT70YFQT")
        (field (name "MANUFACTURER") "Texas Instruments")
        (field (name "PARTNUMBER") "LMT70YFQR")
        (field (name "PUBLISHER") "Texas Instruments")
      )
      (libsource (lib "Altium Vault - TI") (part "LMT70"))
    )
    (comp (ref "U11")
      (value "INA826AIDGK")
      (footprint "DGK0008A_N")
      (description "Precision, 200-μA Supply Current, 36-V Supply Instrumentation Amplifier, DGK0008A (VSSOP-8)")
      (fields (field (name "PARTNUMBER") "INA826AIDGK") (field (name "MANUFACTURER") "Texas Instruments"))
      (libsource (lib "Altium Vault - TI") (part "INA826"))
    )
    (comp (ref "U12")
      (value "REF6241IDGKR")
      (footprint "DGK0008A_N")
      (description "High-Precision Voltage Reference with Integrated High-Bandwidth Buffer, DGK0008A (VSSOP-8)")
      (fields
        (field (name "ALTERNATE PARTNUMBER") "REF6241IDGKT")
        (field (name "MANUFACTURER") "Texas Instruments")
        (field (name "PARTNUMBER") "REF6241IDGKR")
      )
      (libsource (lib "Altium Vault - TI") (part "REF62xx"))
    )
    (comp (ref "U16")
      (value "INA826AIDGK")
      (footprint "DGK0008A_N")
      (description "Precision, 200-μA Supply Current, 36-V Supply Instrumentation Amplifier, DGK0008A (VSSOP-8)")
      (fields (field (name "PARTNUMBER") "INA826AIDGK") (field (name "MANUFACTURER") "Texas Instruments"))
      (libsource (lib "Altium Vault - TI") (part "INA826"))
    )
    (comp (ref "U17")
      (value "OPA188AID")
      (footprint "D0008A_N")
      (fields (field (name "MANUFACTURER") "Texas Instruments") (field (name "PARTNUMBER") "OPA188AID"))
      (libsource (lib "Altium Vault - TI") (part "TI-OPA188-D8"))
    )
    (comp (ref "U18")
      (value "LM2903DR")
      (footprint "D0008A_N")
      (description "Dual Comparator, D0008A")
      (fields
        (field (name "MANUFACTURER") "Texas Instruments")
        (field (name "PUBLISHER") "Texas Instruments")
      )
      (libsource (lib "NSC Amplifier") (part "LM2903D"))
    )
  )
  (nets
    (net (code "1") (name "+3.3V") (class "Default")
      (node (ref "R104") (pin "2") (pinfunction "2_2") (pintype "passive"))
      (node (ref "R97") (pin "2") (pinfunction "2_2") (pintype "passive"))
    )
    (net (code "2") (name "+5V_CNTL") (class "Default")
      (node (ref "C45") (pin "1") (pinfunction "1_1") (pintype "passive"))
      (node (ref "C54") (pin "2") (pinfunction "2_2") (pintype "passive"))
      (node (ref "C55") (pin "1") (pinfunction "1_1") (pintype "passive"))
      (node (ref "R40") (pin "2") (pinfunction "2_2") (pintype "passive"))
      (node (ref "U10") (pin "A2") (pinfunction "VDD_A2") (pintype "power_in"))
      (node (ref "U12") (pin "1") (pinfunction "VIN_1") (pintype "power_in"))
      (node (ref "U12") (pin "2") (pinfunction "EN_2") (pintype "input"))
      (node (ref "U12") (pin "3") (pinfunction "SS_3") (pintype "passive"))
    )
    (net (code "3") (name "+12V") (class "Default")
      (node (ref "C16") (pin "2") (pinfunction "2_2") (pintype "passive"))
      (node (ref "C52") (pin "1") (pinfunction "1_1") (pintype "passive"))
      (node (ref "C53") (pin "1") (pinfunction "1_1") (pintype "passive"))
      (node (ref "C83") (pin "1") (pinfunction "1_1") (pintype "passive"))
      (node (ref "C84") (pin "1") (pinfunction "1_1") (pintype "passive"))
      (node (ref "C86") (pin "2") (pinfunction "2_2") (pintype "passive"))
      (node (ref "C90") (pin "2") (pinfunction "2_2") (pintype "passive"))
      (node (ref "R103") (pin "2") (pinfunction "2_2") (pintype "passive"))
      (node (ref "R96") (pin "2") (pinfunction "2_2") (pintype "passive"))
      (node (ref "U11") (pin "8") (pinfunction "+VS_8") (pintype "power_in"))
      (node (ref "U16") (pin "8") (pinfunction "+VS_8") (pintype "power_in"))
      (node (ref "U17") (pin "7") (pinfunction "V+_7") (pintype "power_in"))
      (node (ref "U18") (pin "8") (pinfunction "V+_8") (pintype "power_in"))
      (node (ref "U7") (pin "7") (pinfunction "V+_7") (pintype "power_in"))
    )
    (net (code "4") (name "-12V") (class "Default")
      (node (ref "C17") (pin "2") (pinfunction "2_2") (pintype "passive"))
      (node (ref "C39") (pin "1") (pinfunction "1_1") (pintype "passive"))
      (node (ref "C40") (pin "1") (pinfunction "1_1") (pintype "passive"))
      (node (ref "C77") (pin "1") (pinfunction "1_1") (pintype "passive"))
      (node (ref "C78") (pin "1") (pinfunction "1_1") (pintype "passive"))
      (node (ref "C88") (pin "2") (pinfunction "2_2") (pintype "passive"))
      (node (ref "U11") (pin "5") (pinfunction "-VS_5") (pintype "power_in"))
      (node (ref "U16") (pin "5") (pinfunction "-VS_5") (pintype "power_in"))
      (node (ref "U17") (pin "4") (pinfunction "V-_4") (pintype "power_in"))
      (node (ref "U7") (pin "4") (pinfunction "V-_4") (pintype "power_in"))
    )
    (net (code "5") (name "/ADC7") (class "Default")
      (node (ref "C46") (pin "1") (pinfunction "1_1") (pintype "passive"))
      (node (ref "J11") (pin "7") (pinfunction "7_7") (pintype "passive"))
      (node (ref "R42") (pin "2") (pinfunction "2_2") (pintype "passive"))
    )
    (net (code "6") (name "/ADC8") (class "Default")
      (node (ref "C57") (pin "1") (pinfunction "1_1") (pintype "passive"))
      (node (ref "J11") (pin "5") (pinfunction "5_5") (pintype "passive"))
      (node (ref "R50") (pin "2") (pinfunction "2_2") (pintype "passive"))
    )
    (net (code "7") (name "/CT_1_OUT") (class "Default")
      (node (ref "C82") (pin "1") (pinfunction "1_1") (pintype "passive"))
      (node (ref "J11") (pin "3") (pinfunction "3_3") (pintype "passive"))
      (node (ref "R81") (pin "2") (pinfunction "2_2") (pintype "passive"))
    )
    (net (code "8") (name "/CT_2_OUT") (class "Default")
      (node (ref "C87") (pin "1") (pinfunction "1_1") (pintype "passive"))
      (node (ref "J11") (pin "1") (pinfunction "1_1") (pintype "passive"))
      (node (ref "R92") (pin "2") (pinfunction "2_2") (pintype "passive"))
    )
    (net (code "9") (name "/PD_OUT1_ZC") (class "Default")
      (node (ref "R98") (pin "1") (pinfunction "1_1") (pintype "passive"))
    )
    (net (code "10") (name "/PD_OUT2_ZC") (class "Default")
      (node (ref "R105") (pin "1") (pinfunction "1_1") (pintype "passive"))
    )
    (net (code "11") (name "AGND") (class "Default")
      (node (ref "C16") (pin "1") (pinfunction "1_1") (pintype "passive"))
      (node (ref "C17") (pin "1") (pinfunction "1_1") (pintype "passive"))
      (node (ref "C18") (pin "1") (pinfunction "1_1") (pintype "passive"))
      (node (ref "C39") (pin "2") (pinfunction "2_2") (pintype "passive"))
      (node (ref "C40") (pin "2") (pinfunction "2_2") (pintype "passive"))
      (node (ref "C45") (pin "2") (pinfunction "2_2") (pintype "passive"))
      (node (ref "C46") (pin "2") (pinfunction "2_2") (pintype "passive"))
      (node (ref "C52") (pin "2") (pinfunction "2_2") (pintype "passive"))
      (node (ref "C53") (pin "2") (pinfunction "2_2") (pintype "passive"))
      (node (ref "C54") (pin "1") (pinfunction "1_1") (pintype "passive"))
      (node (ref "C55") (pin "2") (pinfunction "2_2") (pintype "passive"))
      (node (ref "C56") (pin "1") (pinfunction "1_1") (pintype "passive"))
      (node (ref "C57") (pin "2") (pinfunction "2_2") (pintype "passive"))
      (node (ref "C58") (pin "1") (pinfunction "1_1") (pintype "passive"))
      (node (ref "C77") (pin "2") (pinfunction "2_2") (pintype "passive"))
      (node (ref "C78") (pin "2") (pinfunction "2_2") (pintype "passive"))
      (node (ref "C79") (pin "2") (pinfunction "2_2") (pintype "passive"))
      (node (ref "C81") (pin "1") (pinfunction "1_1") (pintype "passive"))
      (node (ref "C82") (pin "2") (pinfunction "2_2") (pintype "passive"))
      (node (ref "C83") (pin "2") (pinfunction "2_2") (pintype "passive"))
      (node (ref "C84") (pin "2") (pinfunction "2_2") (pintype "passive"))
      (node (ref "C86") (pin "1") (pinfunction "1_1") (pintype "passive"))
      (node (ref "C87") (pin "2") (pinfunction "2_2") (pintype "passive"))
      (node (ref "C88") (pin "1") (pinfunction "1_1") (pintype "passive"))
      (node (ref "C89") (pin "1") (pinfunction "1_1") (pintype "passive"))
      (node (ref "C90") (pin "1") (pinfunction "1_1") (pintype "passive"))
      (node (ref "C91") (pin "1") (pinfunction "1_1") (pintype "passive"))
      (node (ref "D10") (pin "2") (pinfunction "A_2") (pintype "passive"))
      (node (ref "D9") (pin "2") (pinfunction "A_2") (pintype "passive"))
      (node (ref "J11") (pin "2") (pinfunction "2_2") (pintype "passive"))
      (node (ref "J11") (pin "4") (pinfunction "4_4") (pintype "passive"))
      (node (ref "J11") (pin "6") (pinfunction "6_6") (pintype "passive"))
      (node (ref "J11") (pin "8") (pinfunction "8_8") (pintype "passive"))
      (node (ref "R100") (pin "1") (pinfunction "1_1") (pintype "passive"))
      (node (ref "R107") (pin "1") (pinfunction "1_1") (pintype "passive"))
      (node (ref "R80") (pin "1") (pinfunction "1_1") (pintype "passive"))
      (node (ref "R85") (pin "2") (pinfunction "2_2") (pintype "passive"))
      (node (ref "R94") (pin "2") (pinfunction "2_2") (pintype "passive"))
      (node (ref "R95") (pin "1") (pinfunction "1_1") (pintype "passive"))
      (node (ref "TP12") (pin "1") (pintype "passive"))
      (node (ref "TP27") (pin "1") (pintype "passive"))
      (node (ref "U10") (pin "A1") (pinfunction "GND_A1") (pintype "power_in"))
      (node (ref "U11") (pin "1") (pinfunction "-IN_1") (pintype "input"))
      (node (ref "U11") (pin "6") (pinfunction "REF_6") (pintype "input"))
      (node (ref "U12") (pin "7") (pinfunction "GND_F_7") (pintype "power_in"))
      (node (ref "U12") (pin "8") (pinfunction "GND_S_8") (pintype "input"))
      (node (ref "U16") (pin "6") (pinfunction "REF_6") (pintype "input"))
      (node (ref "U18") (pin "4") (pinfunction "V-_4") (pintype "power_in"))
    )
    (net (code "12") (name "Net-(C18-Pad2)") (class "Default")
      (node (ref "C18") (pin "2") (pinfunction "2_2") (pintype "passive"))
      (node (ref "R105") (pin "2") (pinfunction "2_2") (pintype "passive"))
      (node (ref "R106") (pin "1") (pinfunction "1_1") (pintype "passive"))
    )
    (net (code "13") (name "Net-(C89-Pad2)") (class "Default")
      (node (ref "C89") (pin "2") (pinfunction "2_2") (pintype "passive"))
      (node (ref "R98") (pin "2") (pinfunction "2_2") (pintype "passive"))
      (node (ref "R99") (pin "1") (pinfunction "1_1") (pintype "passive"))
    )
    (net (code "14") (name "Net-(C91-Pad2)") (class "Default")
      (node (ref "C91") (pin "2") (pinfunction "2_2") (pintype "passive"))
      (node (ref "R101") (pin "2") (pinfunction "2_2") (pintype "passive"))
      (node (ref "TP29") (pin "1") (pintype "passive"))
    )
    (net (code "15") (name "Net-(D8-K-Pad1)") (class "Default")
      (node (ref "D8") (pin "1") (pinfunction "K_1") (pintype "passive"))
      (node (ref "JP3") (pin "1") (pinfunction "1_1") (pintype "passive"))
      (node (ref "L7") (pin "1") (pinfunction "1_1") (pintype "passive"))
      (node (ref "R82") (pin "2") (pinfunction "2_2") (pintype "passive"))
      (node (ref "T1") (pin "1") (pinfunction "1_1") (pintype "passive"))
    )
    (net (code "16") (name "Net-(D8-K-Pad2)") (class "Default")
      (node (ref "D8") (pin "2") (pinfunction "K_2") (pintype "passive"))
      (node (ref "L8") (pin "1") (pinfunction "1_1") (pintype "passive"))
      (node (ref "R82") (pin "1") (pinfunction "1_1") (pintype "passive"))
      (node (ref "R84") (pin "1") (pinfunction "1_1") (pintype "passive"))
      (node (ref "T1") (pin "2") (pinfunction "2_2") (pintype "passive"))
    )
    (net (code "17") (name "Net-(D9-K)") (class "Default")
      (node (ref "D9") (pin "1") (pinfunction "K_1") (pintype "passive"))
      (node (ref "R91") (pin "2") (pinfunction "2_2") (pintype "passive"))
      (node (ref "R99") (pin "2") (pinfunction "2_2") (pintype "passive"))
      (node (ref "U18") (pin "3") (pinfunction "IN+_3") (pintype "input"))
    )
    (net (code "18") (name "Net-(D10-K)") (class "Default")
      (node (ref "D10") (pin "1") (pinfunction "K_1") (pintype "passive"))
      (node (ref "R102") (pin "2") (pinfunction "2_2") (pintype "passive"))
      (node (ref "R106") (pin "2") (pinfunction "2_2") (pintype "passive"))
      (node (ref "U18") (pin "5") (pinfunction "IN+_5") (pintype "input"))
    )
    (net (code "19") (name "Net-(J14-Pad2)") (class "Default")
      (node (ref "J14") (pin "2") (pinfunction "2_2") (pintype "passive"))
      (node (ref "J15") (pin "2") (pinfunction "2_2") (pintype "passive"))
      (node (ref "R101") (pin "1") (pinfunction "1_1") (pintype "passive"))
    )
    (net (code "20") (name "Net-(JP3-Pad2)") (class "Default")
      (node (ref "JP3") (pin "2") (pinfunction "2_2") (pintype "passive"))
      (node (ref "R84") (pin "2") (pinfunction "2_2") (pintype "passive"))
    )
    (net (code "21") (name "Net-(L7-Pad2)") (class "Default")
      (node (ref "L7") (pin "2") (pinfunction "2_2") (pintype "passive"))
      (node (ref "R79") (pin "1") (pinfunction "1_1") (pintype "passive"))
    )
    (net (code "22") (name "Net-(L8-Pad2)") (class "Default")
      (node (ref "L8") (pin "2") (pinfunction "2_2") (pintype "passive"))
      (node (ref "R86") (pin "1") (pinfunction "1_1") (pintype "passive"))
    )
    (net (code "23") (name "Net-(R43-Pad1)") (class "Default")
      (node (ref "R43") (pin "1") (pinfunction "1_1") (pintype "passive"))
      (node (ref "U11") (pin "2") (pinfunction "RG_2") (pintype "input"))
    )
    (net (code "24") (name "Net-(R43-Pad2)") (class "Default")
      (node (ref "R43") (pin "2") (pinfunction "2_2") (pintype "passive"))
      (node (ref "U11") (pin "3") (pinfunction "RG_3") (pintype "input"))
    )
    (net (code "25") (name "Net-(R83-Pad1)") (class "Default")
      (node (ref "R83") (pin "1") (pinfunction "1_1") (pintype "passive"))
      (node (ref "U16") (pin "2") (pinfunction "RG_2") (pintype "input"))
    )
    (net (code "26") (name "Net-(R83-Pad2)") (class "Default")
      (node (ref "R83") (pin "2") (pinfunction "2_2") (pintype "passive"))
      (node (ref "U16") (pin "3") (pinfunction "RG_3") (pintype "input"))
    )
    (net (code "27") (name "Net-(R87-Pad1)") (class "Default")
      (node (ref "R87") (pin "1") (pinfunction "1_1") (pintype "passive"))
      (node (ref "R93") (pin "2") (pinfunction "2_2") (pintype "passive"))
    )
    (net (code "28") (name "Net-(R88-Pad1)") (class "Default")
      (node (ref "R88") (pin "1") (pinfunction "1_1") (pintype "passive"))
      (node (ref "R90") (pin "2") (pinfunction "2_2") (pintype "passive"))
      (node (ref "R94") (pin "1") (pinfunction "1_1") (pintype "passive"))
    )
    (net (code "29") (name "Net-(U7A-IN-)") (class "Default")
      (node (ref "R50") (pin "1") (pinfunction "1_1") (pintype "passive"))
      (node (ref "U7") (pin "2") (pinfunction "IN-_2") (pintype "input"))
      (node (ref "U7") (pin "6") (pinfunction "OUT_6") (pintype "output"))
    )
    (net (code "30") (name "Net-(U10-TA0)") (class "Default")
      (node (ref "U10") (pin "B1") (pinfunction "TA0_B1") (pintype "output"))
      (node (ref "U11") (pin "4") (pinfunction "+IN_4") (pintype "input"))
    )
    (net (code "31") (name "Net-(U10-T_ON)") (class "Default")
      (node (ref "R40") (pin "1") (pinfunction "1_1") (pintype "passive"))
      (node (ref "U10") (pin "B2") (pinfunction "T_ON_B2") (pintype "input"))
    )
    (net (code "32") (name "Net-(U11-VOUT)") (class "Default")
      (node (ref "R42") (pin "1") (pinfunction "1_1") (pintype "passive"))
      (node (ref "TP11") (pin "1") (pintype "passive"))
      (node (ref "U11") (pin "7") (pinfunction "VOUT_7") (pintype "output"))
    )
    (net (code "33") (name "Net-(U12-FILT)") (class "Default")
      (node (ref "C58") (pin "2") (pinfunction "2_2") (pintype "passive"))
      (node (ref "U12") (pin "4") (pinfunction "FILT_4") (pintype "passive"))
    )
    (net (code "34") (name "Net-(U12-OUT_F)") (class "Default")
      (node (ref "C56") (pin "2") (pinfunction "2_2") (pintype "passive"))
      (node (ref "TP13") (pin "1") (pintype "passive"))
      (node (ref "U12") (pin "5") (pinfunction "OUT_S_5") (pintype "input"))
      (node (ref "U12") (pin "6") (pinfunction "OUT_F_6") (pintype "output"))
      (node (ref "U7") (pin "3") (pinfunction "IN+_3") (pintype "input"))
    )
    (net (code "35") (name "Net-(U16-+IN)") (class "Default")
      (node (ref "C79") (pin "1") (pinfunction "1_1") (pintype "passive"))
      (node (ref "C80") (pin "1") (pinfunction "1_1") (pintype "passive"))
      (node (ref "R79") (pin "2") (pinfunction "2_2") (pintype "passive"))
      (node (ref "R80") (pin "2") (pinfunction "2_2") (pintype "passive"))
      (node (ref "R87") (pin "2") (pinfunction "2_2") (pintype "passive"))
      (node (ref "TP24") (pin "1") (pintype "passive"))
      (node (ref "U16") (pin "4") (pinfunction "+IN_4") (pintype "input"))
    )
    (net (code "36") (name "Net-(U16--IN)") (class "Default")
      (node (ref "C80") (pin "2") (pinfunction "2_2") (pintype "passive"))
      (node (ref "C81") (pin "2") (pinfunction "2_2") (pintype "passive"))
      (node (ref "R85") (pin "1") (pinfunction "1_1") (pintype "passive"))
      (node (ref "R86") (pin "2") (pinfunction "2_2") (pintype "passive"))
      (node (ref "R88") (pin "2") (pinfunction "2_2") (pintype "passive"))
      (node (ref "TP26") (pin "1") (pintype "passive"))
      (node (ref "U16") (pin "1") (pinfunction "-IN_1") (pintype "input"))
    )
    (net (code "37") (name "Net-(U16-VOUT)") (class "Default")
      (node (ref "R81") (pin "1") (pinfunction "1_1") (pintype "passive"))
      (node (ref "TP25") (pin "1") (pintype "passive"))
      (node (ref "U16") (pin "7") (pinfunction "VOUT_7") (pintype "output"))
    )
    (net (code "38") (name "Net-(U17A-IN+)") (class "Default")
      (node (ref "R93") (pin "1") (pinfunction "1_1") (pintype "passive"))
      (node (ref "R95") (pin "2") (pinfunction "2_2") (pintype "passive"))
      (node (ref "U17") (pin "3") (pinfunction "IN+_3") (pintype "input"))
    )
    (net (code "39") (name "Net-(U17A-IN-)") (class "Default")
      (node (ref "C85") (pin "1") (pinfunction "1_1") (pintype "passive"))
      (node (ref "R89") (pin "2") (pinfunction "2_2") (pintype "passive"))
      (node (ref "R90") (pin "1") (pinfunction "1_1") (pintype "passive"))
      (node (ref "U17") (pin "2") (pinfunction "IN-_2") (pintype "input"))
    )
    (net (code "40") (name "Net-(U17A-OUT)") (class "Default")
      (node (ref "C85") (pin "2") (pinfunction "2_2") (pintype "passive"))
      (node (ref "R89") (pin "1") (pinfunction "1_1") (pintype "passive"))
      (node (ref "R92") (pin "1") (pinfunction "1_1") (pintype "passive"))
      (node (ref "TP28") (pin "1") (pintype "passive"))
      (node (ref "U17") (pin "6") (pinfunction "OUT_6") (pintype "output"))
    )
    (net (code "41") (name "Net-(U18A-IN-)") (class "Default")
      (node (ref "R100") (pin "2") (pinfunction "2_2") (pintype "passive"))
      (node (ref "R96") (pin "1") (pinfunction "1_1") (pintype "passive"))
      (node (ref "U18") (pin "2") (pinfunction "IN-_2") (pintype "input"))
    )
    (net (code "42") (name "Net-(U18A-OUT)") (class "Default")
      (node (ref "J14") (pin "1") (pinfunction "1_1") (pintype "passive"))
      (node (ref "R91") (pin "1") (pinfunction "1_1") (pintype "passive"))
      (node (ref "R97") (pin "1") (pinfunction "1_1") (pintype "passive"))
      (node (ref "U18") (pin "1") (pinfunction "OUT_1") (pintype "output"))
    )
    (net (code "43") (name "Net-(U18B-IN-)") (class "Default")
      (node (ref "R103") (pin "1") (pinfunction "1_1") (pintype "passive"))
      (node (ref "R107") (pin "2") (pinfunction "2_2") (pintype "passive"))
      (node (ref "U18") (pin "6") (pinfunction "IN-_6") (pintype "input"))
    )
    (net (code "44") (name "Net-(U18B-OUT)") (class "Default")
      (node (ref "J15") (pin "1") (pinfunction "1_1") (pintype "passive"))
      (node (ref "R102") (pin "1") (pinfunction "1_1") (pintype "passive"))
      (node (ref "R104") (pin "1") (pinfunction "1_1") (pintype "passive"))
      (node (ref "U18") (pin "7") (pinfunction "OUT_7") (pintype "output"))
    )
    (net (code "45") (name "unconnected-(T1-Pad3)") (class "Default")
      (node (ref "T1") (pin "3") (pinfunction "3_3") (pintype "passive"))
    )
    (net (code "46") (name "unconnected-(T1-Pad4)") (class "Default")
      (node (ref "T1") (pin "4") (pinfunction "4_4") (pintype "passive"))
    )
    (net (code "47") (name "unconnected-(U7B-NC-Pad1)") (class "Default")
      (node (ref "U7") (pin "1") (pinfunction "NC_1") (pintype "passive"))
    )
    (net (code "48") (name "unconnected-(U7B-NC-Pad5)") (class "Default")
      (node (ref "U7") (pin "5") (pinfunction "NC_5") (pintype "passive"))
    )
    (net (code "49") (name "unconnected-(U7B-NC-Pad8)") (class "Default")
      (node (ref "U7") (pin "8") (pinfunction "NC_8") (pintype "passive"))
    )
    (net (code "50") (name "unconnected-(U17B-NC-Pad1)") (class "Default")
      (node (ref "U17") (pin "1") (pinfunction "NC_1") (pintype "passive"))
    )
    (net (code "51") (name "unconnected-(U17B-NC-Pad5)") (class "Default")
      (node (ref "U17") (pin "5") (pinfunction "NC_5") (pintype "passive"))
    )
    (net (code "52") (name "unconnected-(U17B-NC-Pad8)") (class "Default")
      (node (ref "U17") (pin "8") (pinfunction "NC_8") (pintype "passive"))
    )
    (net (code "53") (name "unconnected-(U18B-V+-Pad8)") (class "Default")
      (node (ref "U18") (pin "8") (pinfunction "V+_8") (pintype "power_in"))
    )
    (net (code "54") (name "unconnected-(U18B-V--Pad4)") (class "Default")
      (node (ref "U18") (pin "4") (pinfunction "V-_4") (pintype "power_in"))
    )
  )
)
